# main.net
KiCad netlist of a schematic drawn in EAGLE
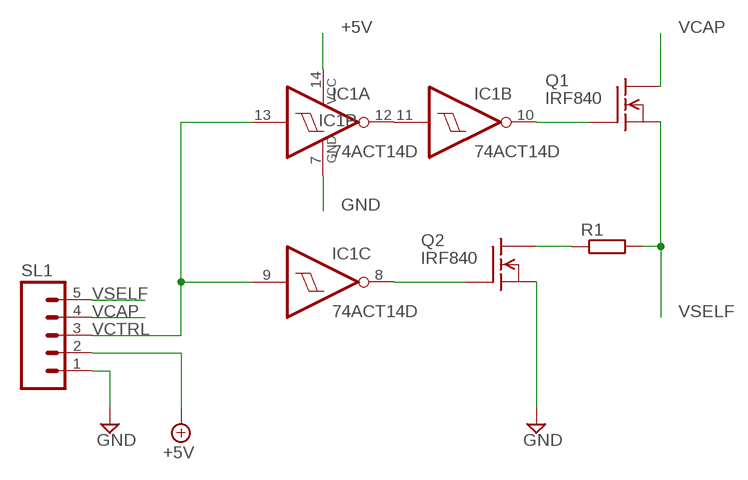
[diagram p0: schematic, sheet 1]

(export (version "E")
  (design (tool "Eeschema 10.0.6"))
  (components
    (comp (ref "IC1")
      (value "74ACT14D")
      (footprint "eagle-import:SO14")
      (libsource (lib "eagle-import") (part "7414DACT"))
    )
    (comp (ref "Q1")
      (value "IRF840")
      (footprint "eagle-import:TO220")
      (libsource (lib "eagle-import") (part "IRF840"))
    )
    (comp (ref "Q2")
      (value "IRF840")
      (footprint "eagle-import:TO220")
      (libsource (lib "eagle-import") (part "IRF840"))
    )
    (comp (ref "R1")
      (value "R-EU_0204/5")
      (footprint "eagle-import:0204_5")
      (libsource (lib "eagle-import") (part "R-EU_0204/5"))
    )
    (comp (ref "SL1")
      (value "M05")
      (footprint "eagle-import:05P")
      (libsource (lib "eagle-import") (part "M05"))
    )
  )
  (nets
    (net (code "1") (name "+5V") (class "Default")
      (node (ref "IC1") (pin "14") (pinfunction "VCC_14") (pintype "power_in"))
      (node (ref "SL1") (pin "2") (pinfunction "2_2") (pintype "passive"))
    )
    (net (code "2") (name "/VCAP") (class "Default")
      (node (ref "Q1") (pin "2") (pinfunction "D_2") (pintype "passive"))
      (node (ref "SL1") (pin "4") (pinfunction "4_4") (pintype "passive"))
    )
    (net (code "3") (name "/VCTRL") (class "Default")
      (node (ref "IC1") (pin "13") (pinfunction "I_13") (pintype "input"))
      (node (ref "IC1") (pin "9") (pinfunction "I_9") (pintype "input"))
      (node (ref "SL1") (pin "3") (pinfunction "3_3") (pintype "passive"))
    )
    (net (code "4") (name "/VSELF") (class "Default")
      (node (ref "Q1") (pin "3") (pinfunction "S_3") (pintype "passive"))
      (node (ref "R1") (pin "2") (pinfunction "2_2") (pintype "passive"))
      (node (ref "SL1") (pin "5") (pinfunction "5_5") (pintype "passive"))
    )
    (net (code "5") (name "GND") (class "Default")
      (node (ref "IC1") (pin "7") (pinfunction "GND_7") (pintype "power_in"))
      (node (ref "Q2") (pin "3") (pinfunction "S_3") (pintype "passive"))
      (node (ref "SL1") (pin "1") (pinfunction "1_1") (pintype "passive"))
    )
    (net (code "6") (name "Net-(IC1A-O)") (class "Default")
      (node (ref "IC1") (pin "11") (pinfunction "I_11") (pintype "input"))
      (node (ref "IC1") (pin "12") (pinfunction "O_12") (pintype "output"))
    )
    (net (code "7") (name "Net-(IC1B-O)") (class "Default")
      (node (ref "IC1") (pin "10") (pinfunction "O_10") (pintype "output"))
      (node (ref "Q1") (pin "1") (pinfunction "G_1") (pintype "passive"))
    )
    (net (code "8") (name "Net-(IC1C-O)") (class "Default")
      (node (ref "IC1") (pin "8") (pinfunction "O_8") (pintype "output"))
      (node (ref "Q2") (pin "1") (pinfunction "G_1") (pintype "passive"))
    )
    (net (code "9") (name "Net-(Q2-D)") (class "Default")
      (node (ref "Q2") (pin "2") (pinfunction "D_2") (pintype "passive"))
      (node (ref "R1") (pin "1") (pinfunction "1_1") (pintype "passive"))
    )
  )
)
